# LED.net
KiCad netlist of a schematic drawn in Altium Designer
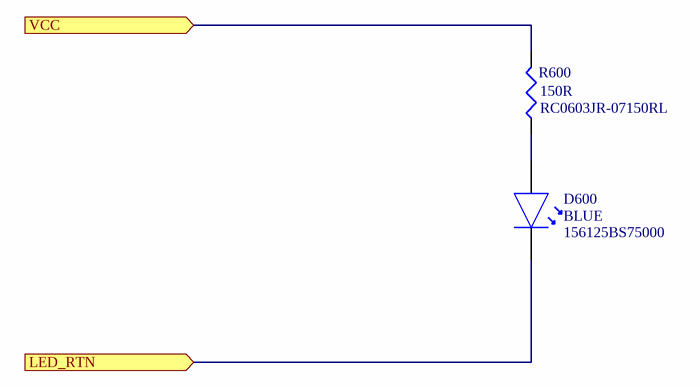
[diagram p0: LED.SchDoc]

(export (version "E")
  (design (tool "Eeschema 10.0.6"))
  (components
    (comp (ref "D600")
      (value "BLUE")
      (footprint "WL-SMRW_1205_BLU")
      (description "WL-SMRW SMD MONO-COLOR REVERSE MOUNT. Blue 470nm LED Indication - Discrete 3.2V 1205 (3212 Metric)")
      (fields (field (name "MANUFACTURER PART NUMBER 1") "156125BS75000"))
      (libsource (lib "CubeSat-Backplane") (part "156125BS75000"))
    )
    (comp (ref "R600")
      (value "150R")
      (footprint "0603")
      (description "RES SMD 150 OHM 5% 1/10W 0603")
      (fields (field (name "MANUFACTURER PART NUMBER 1") "RC0603JR-07150RL") (field (name "TOLERANCE") "5%"))
      (libsource (lib "CubeSat-Backplane") (part "RES1"))
    )
  )
  (nets
    (net (code "1") (name "/LED_RTN") (class "Default")
      (node (ref "D600") (pin "K") (pinfunction "K_K") (pintype "passive"))
    )
    (net (code "2") (name "/VCC") (class "Default")
      (node (ref "R600") (pin "2") (pinfunction "2_2") (pintype "passive"))
    )
    (net (code "3") (name "Net-(D600-PadA)") (class "Default")
      (node (ref "D600") (pin "A") (pinfunction "A_A") (pintype "passive"))
      (node (ref "R600") (pin "1") (pinfunction "1_1") (pintype "passive"))
    )
  )
)
